# ProProject_jlc_phxc_2024-02-14.net
KiCad netlist of a schematic drawn in EasyEDA Pro
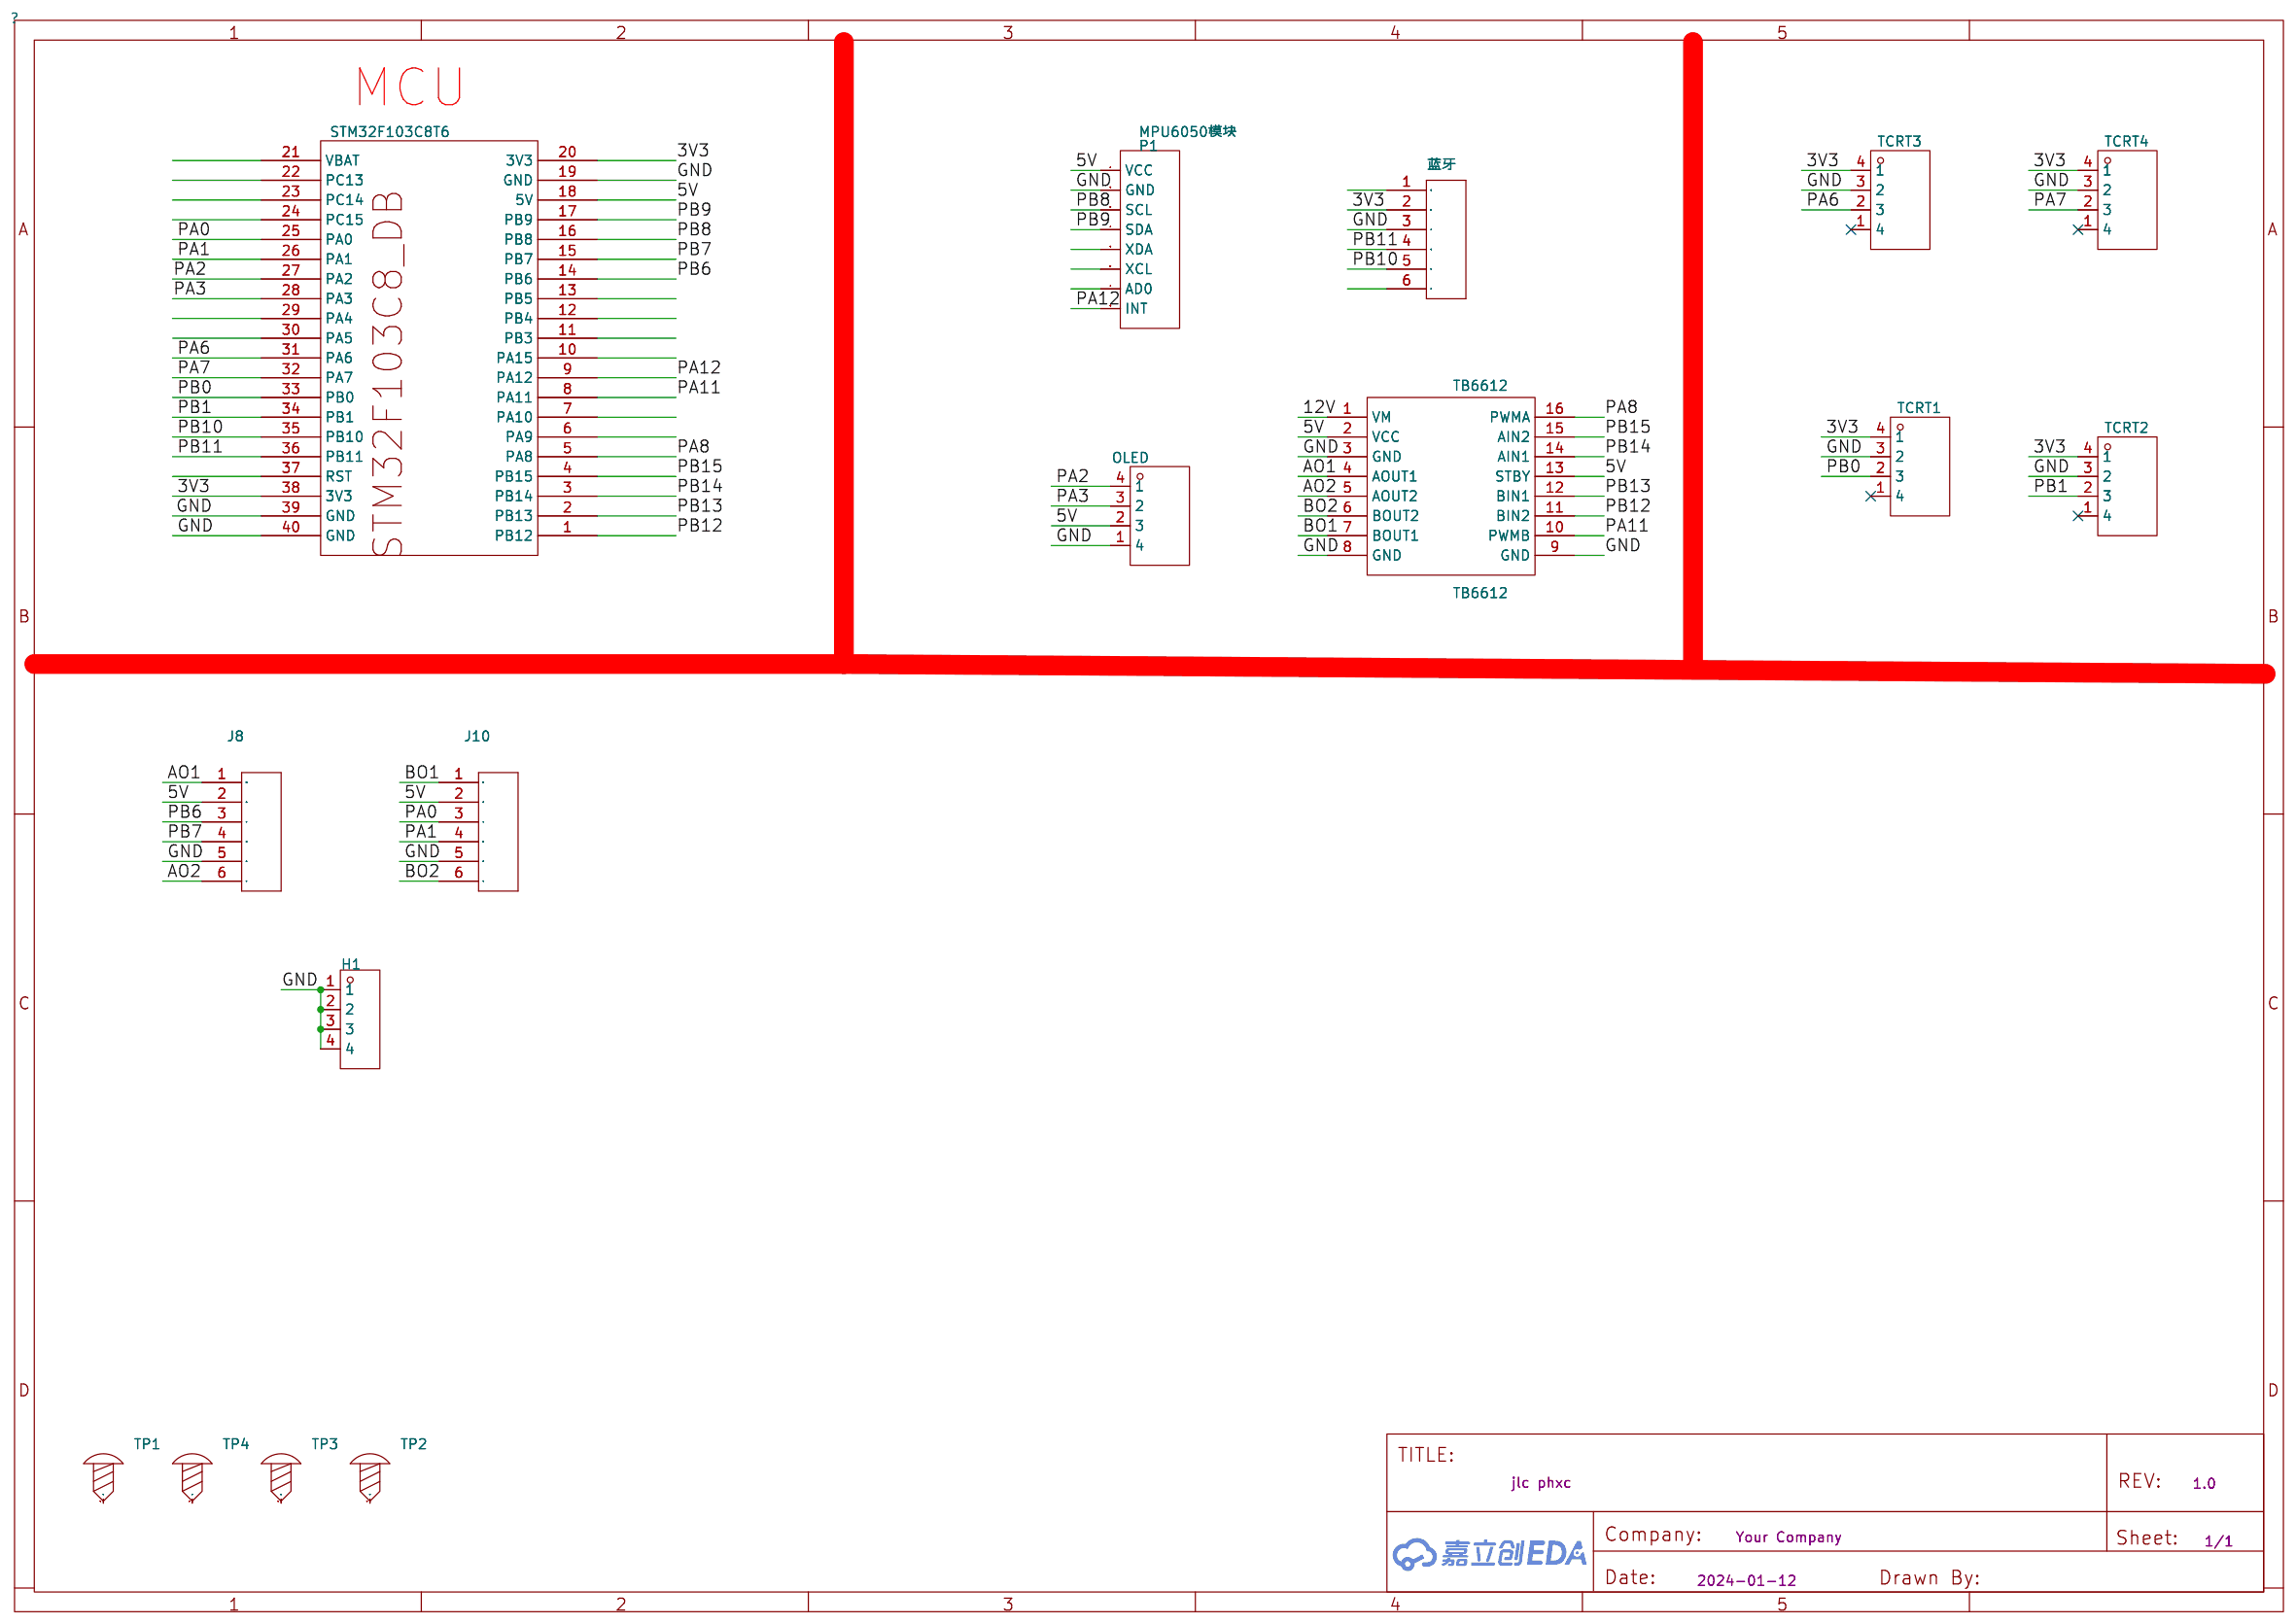
[diagram p0: schematic sheet]

(export (version "E")
  (design (tool "Eeschema 10.0.6"))
  (components
    (comp (ref "1")
      (value "TCRT1")
      (footprint "easyedapro:TCRT5000-红外循迹模块")
      (libsource (lib "easyedapro") (part "TCRT1"))
    )
    (comp (ref "2")
      (value "TCRT2")
      (footprint "easyedapro:TCRT5000-红外循迹模块")
      (libsource (lib "easyedapro") (part "TCRT2"))
    )
    (comp (ref "3")
      (value "TCRT3")
      (footprint "easyedapro:TCRT5000-红外循迹模块")
      (libsource (lib "easyedapro") (part "TCRT3"))
    )
    (comp (ref "4")
      (value "TCRT4")
      (footprint "easyedapro:TCRT5000-红外循迹模块")
      (libsource (lib "easyedapro") (part "TCRT4"))
    )
    (comp (ref "H1")
      (value "~")
      (footprint "easyedapro:HDR-TH_4P-P2.54-V-F")
      (libsource (lib "easyedapro") (part "2.54-1*4P母"))
    )
    (comp (ref "J8")
      (value "F185-1106A1BRYA1")
      (footprint "easyedapro:H6-2.54-90D-FEMALE")
      (libsource (lib "easyedapro") (part "F185-1106A1BRYA1"))
    )
    (comp (ref "J10")
      (value "F185-1106A1BRYA1")
      (footprint "easyedapro:H6-2.54-90D-FEMALE")
      (libsource (lib "easyedapro") (part "F185-1106A1BRYA1"))
    )
    (comp (ref "OLEDU1")
      (value "OLED")
      (footprint "easyedapro:0.96OLED_4P")
      (libsource (lib "easyedapro") (part "OLED"))
    )
    (comp (ref "P1")
      (value "MPU6050模块")
      (footprint "easyedapro:MPU6050模块")
      (libsource (lib "easyedapro") (part "MPU6050模块"))
    )
    (comp (ref "STMSTM32F103C8_DB")
      (value "STM32F103C8T6")
      (footprint "easyedapro:STM32F103C8T6_DB")
      (libsource (lib "easyedapro") (part "STM32F103C8_DB"))
    )
    (comp (ref "TB6612")
      (value "TB6612")
      (footprint "easyedapro:COMM-TH_TB6612")
      (libsource (lib "easyedapro") (part "TB6612"))
    )
    (comp (ref "TP1") (value "~") (footprint "easyedapro:M3螺丝") (libsource (lib "easyedapro") (part "螺丝孔")))
    (comp (ref "TP2") (value "~") (footprint "easyedapro:M3螺丝") (libsource (lib "easyedapro") (part "螺丝孔")))
    (comp (ref "TP3") (value "~") (footprint "easyedapro:M3螺丝") (libsource (lib "easyedapro") (part "螺丝孔")))
    (comp (ref "TP4") (value "~") (footprint "easyedapro:M3螺丝") (libsource (lib "easyedapro") (part "螺丝孔")))
    (comp (ref "蓝牙")
      (value "F185-1106A1BRYA1")
      (footprint "easyedapro:H6-2.54-90D-FEMALE")
      (libsource (lib "easyedapro") (part "F185-1106A1BRYA1"))
    )
  )
  (nets
    (net (code "1") (name "/3V3") (class "Default")
      (node (ref "1") (pin "4") (pinfunction "1_4") (pintype "unspecified"))
      (node (ref "2") (pin "4") (pinfunction "1_4") (pintype "unspecified"))
      (node (ref "3") (pin "4") (pinfunction "1_4") (pintype "unspecified"))
      (node (ref "4") (pin "4") (pinfunction "1_4") (pintype "unspecified"))
      (node (ref "STMSTM32F103C8_DB") (pin "20") (pinfunction "3V3_20") (pintype "unspecified"))
      (node (ref "STMSTM32F103C8_DB") (pin "38") (pinfunction "3V3_38") (pintype "unspecified"))
      (node (ref "蓝牙") (pin "2") (pinfunction "5_2") (pintype "unspecified"))
    )
    (net (code "2") (name "/5V") (class "Default")
      (node (ref "J10") (pin "2") (pinfunction "5_2") (pintype "unspecified"))
      (node (ref "J8") (pin "2") (pinfunction "5_2") (pintype "unspecified"))
      (node (ref "OLEDU1") (pin "2") (pinfunction "3_2") (pintype "unspecified"))
      (node (ref "P1") (pin "1") (pinfunction "VCC_1") (pintype "input"))
      (node (ref "STMSTM32F103C8_DB") (pin "18") (pinfunction "5V_18") (pintype "unspecified"))
      (node (ref "TB6612") (pin "13") (pinfunction "STBY_13") (pintype "unspecified"))
      (node (ref "TB6612") (pin "2") (pinfunction "VCC_2") (pintype "unspecified"))
    )
    (net (code "3") (name "/12V") (class "Default")
      (node (ref "TB6612") (pin "1") (pinfunction "VM_1") (pintype "unspecified"))
    )
    (net (code "4") (name "/AO1") (class "Default")
      (node (ref "J8") (pin "1") (pinfunction "6_1") (pintype "unspecified"))
      (node (ref "TB6612") (pin "4") (pinfunction "AOUT1_4") (pintype "unspecified"))
    )
    (net (code "5") (name "/AO2") (class "Default")
      (node (ref "J8") (pin "6") (pinfunction "1_6") (pintype "unspecified"))
      (node (ref "TB6612") (pin "5") (pinfunction "AOUT2_5") (pintype "unspecified"))
    )
    (net (code "6") (name "/BO1") (class "Default")
      (node (ref "J10") (pin "1") (pinfunction "6_1") (pintype "unspecified"))
      (node (ref "TB6612") (pin "7") (pinfunction "BOUT1_7") (pintype "unspecified"))
    )
    (net (code "7") (name "/BO2") (class "Default")
      (node (ref "J10") (pin "6") (pinfunction "1_6") (pintype "unspecified"))
      (node (ref "TB6612") (pin "6") (pinfunction "BOUT2_6") (pintype "unspecified"))
    )
    (net (code "8") (name "/GND") (class "Default")
      (node (ref "1") (pin "3") (pinfunction "2_3") (pintype "unspecified"))
      (node (ref "2") (pin "3") (pinfunction "2_3") (pintype "unspecified"))
      (node (ref "3") (pin "3") (pinfunction "2_3") (pintype "unspecified"))
      (node (ref "4") (pin "3") (pinfunction "2_3") (pintype "unspecified"))
      (node (ref "H1") (pin "1") (pinfunction "1_1") (pintype "unspecified"))
      (node (ref "H1") (pin "2") (pinfunction "2_2") (pintype "unspecified"))
      (node (ref "H1") (pin "3") (pinfunction "3_3") (pintype "unspecified"))
      (node (ref "H1") (pin "4") (pinfunction "4_4") (pintype "unspecified"))
      (node (ref "J10") (pin "5") (pinfunction "2_5") (pintype "unspecified"))
      (node (ref "J8") (pin "5") (pinfunction "2_5") (pintype "unspecified"))
      (node (ref "OLEDU1") (pin "1") (pinfunction "4_1") (pintype "unspecified"))
      (node (ref "P1") (pin "2") (pinfunction "GND_2") (pintype "input"))
      (node (ref "STMSTM32F103C8_DB") (pin "19") (pinfunction "GND_19") (pintype "unspecified"))
      (node (ref "STMSTM32F103C8_DB") (pin "39") (pinfunction "GND_39") (pintype "unspecified"))
      (node (ref "STMSTM32F103C8_DB") (pin "40") (pinfunction "GND_40") (pintype "unspecified"))
      (node (ref "TB6612") (pin "3") (pinfunction "GND_3") (pintype "unspecified"))
      (node (ref "TB6612") (pin "8") (pinfunction "GND_8") (pintype "unspecified"))
      (node (ref "TB6612") (pin "9") (pinfunction "GND_9") (pintype "unspecified"))
      (node (ref "蓝牙") (pin "3") (pinfunction "4_3") (pintype "unspecified"))
    )
    (net (code "9") (name "/PA0") (class "Default")
      (node (ref "J10") (pin "3") (pinfunction "4_3") (pintype "unspecified"))
      (node (ref "STMSTM32F103C8_DB") (pin "25") (pinfunction "PA0_25") (pintype "unspecified"))
    )
    (net (code "10") (name "/PA1") (class "Default")
      (node (ref "J10") (pin "4") (pinfunction "3_4") (pintype "unspecified"))
      (node (ref "STMSTM32F103C8_DB") (pin "26") (pinfunction "PA1_26") (pintype "unspecified"))
    )
    (net (code "11") (name "/PA2") (class "Default")
      (node (ref "OLEDU1") (pin "4") (pinfunction "1_4") (pintype "unspecified"))
      (node (ref "STMSTM32F103C8_DB") (pin "27") (pinfunction "PA2_27") (pintype "unspecified"))
    )
    (net (code "12") (name "/PA3") (class "Default")
      (node (ref "OLEDU1") (pin "3") (pinfunction "2_3") (pintype "unspecified"))
      (node (ref "STMSTM32F103C8_DB") (pin "28") (pinfunction "PA3_28") (pintype "unspecified"))
    )
    (net (code "13") (name "/PA6") (class "Default")
      (node (ref "3") (pin "2") (pinfunction "3_2") (pintype "unspecified"))
      (node (ref "STMSTM32F103C8_DB") (pin "31") (pinfunction "PA6_31") (pintype "unspecified"))
    )
    (net (code "14") (name "/PA7") (class "Default")
      (node (ref "4") (pin "2") (pinfunction "3_2") (pintype "unspecified"))
      (node (ref "STMSTM32F103C8_DB") (pin "32") (pinfunction "PA7_32") (pintype "unspecified"))
    )
    (net (code "15") (name "/PA8") (class "Default")
      (node (ref "STMSTM32F103C8_DB") (pin "5") (pinfunction "PA8_5") (pintype "unspecified"))
      (node (ref "TB6612") (pin "16") (pinfunction "PWMA_16") (pintype "unspecified"))
    )
    (net (code "16") (name "/PA11") (class "Default")
      (node (ref "STMSTM32F103C8_DB") (pin "8") (pinfunction "PA11_8") (pintype "unspecified"))
      (node (ref "TB6612") (pin "10") (pinfunction "PWMB_10") (pintype "unspecified"))
    )
    (net (code "17") (name "/PA12") (class "Default")
      (node (ref "P1") (pin "8") (pinfunction "INT_8") (pintype "input"))
      (node (ref "STMSTM32F103C8_DB") (pin "9") (pinfunction "PA12_9") (pintype "unspecified"))
    )
    (net (code "18") (name "/PB0") (class "Default")
      (node (ref "1") (pin "2") (pinfunction "3_2") (pintype "unspecified"))
      (node (ref "STMSTM32F103C8_DB") (pin "33") (pinfunction "PB0_33") (pintype "unspecified"))
    )
    (net (code "19") (name "/PB1") (class "Default")
      (node (ref "2") (pin "2") (pinfunction "3_2") (pintype "unspecified"))
      (node (ref "STMSTM32F103C8_DB") (pin "34") (pinfunction "PB1_34") (pintype "unspecified"))
    )
    (net (code "20") (name "/PB6") (class "Default")
      (node (ref "J8") (pin "3") (pinfunction "4_3") (pintype "unspecified"))
      (node (ref "STMSTM32F103C8_DB") (pin "14") (pinfunction "PB6_14") (pintype "unspecified"))
    )
    (net (code "21") (name "/PB7") (class "Default")
      (node (ref "J8") (pin "4") (pinfunction "3_4") (pintype "unspecified"))
      (node (ref "STMSTM32F103C8_DB") (pin "15") (pinfunction "PB7_15") (pintype "unspecified"))
    )
    (net (code "22") (name "/PB8") (class "Default")
      (node (ref "P1") (pin "3") (pinfunction "SCL_3") (pintype "input"))
      (node (ref "STMSTM32F103C8_DB") (pin "16") (pinfunction "PB8_16") (pintype "unspecified"))
    )
    (net (code "23") (name "/PB9") (class "Default")
      (node (ref "P1") (pin "4") (pinfunction "SDA_4") (pintype "input"))
      (node (ref "STMSTM32F103C8_DB") (pin "17") (pinfunction "PB9_17") (pintype "unspecified"))
    )
    (net (code "24") (name "/PB10") (class "Default")
      (node (ref "STMSTM32F103C8_DB") (pin "35") (pinfunction "PB10_35") (pintype "unspecified"))
      (node (ref "蓝牙") (pin "5") (pinfunction "2_5") (pintype "unspecified"))
    )
    (net (code "25") (name "/PB11") (class "Default")
      (node (ref "STMSTM32F103C8_DB") (pin "36") (pinfunction "PB11_36") (pintype "unspecified"))
      (node (ref "蓝牙") (pin "4") (pinfunction "3_4") (pintype "unspecified"))
    )
    (net (code "26") (name "/PB12") (class "Default")
      (node (ref "STMSTM32F103C8_DB") (pin "1") (pinfunction "PB12_1") (pintype "unspecified"))
      (node (ref "TB6612") (pin "11") (pinfunction "BIN2_11") (pintype "unspecified"))
    )
    (net (code "27") (name "/PB13") (class "Default")
      (node (ref "STMSTM32F103C8_DB") (pin "2") (pinfunction "PB13_2") (pintype "unspecified"))
      (node (ref "TB6612") (pin "12") (pinfunction "BIN1_12") (pintype "unspecified"))
    )
    (net (code "28") (name "/PB14") (class "Default")
      (node (ref "STMSTM32F103C8_DB") (pin "3") (pinfunction "PB14_3") (pintype "unspecified"))
      (node (ref "TB6612") (pin "14") (pinfunction "AIN1_14") (pintype "unspecified"))
    )
    (net (code "29") (name "/PB15") (class "Default")
      (node (ref "STMSTM32F103C8_DB") (pin "4") (pinfunction "PB15_4") (pintype "unspecified"))
      (node (ref "TB6612") (pin "15") (pinfunction "AIN2_15") (pintype "unspecified"))
    )
    (net (code "30") (name "unconnected-(1-4-Pad1)") (class "Default")
      (node (ref "1") (pin "1") (pinfunction "4_1") (pintype "unspecified+no_connect"))
    )
    (net (code "31") (name "unconnected-(2-4-Pad1)") (class "Default")
      (node (ref "2") (pin "1") (pinfunction "4_1") (pintype "unspecified+no_connect"))
    )
    (net (code "32") (name "unconnected-(3-4-Pad1)") (class "Default")
      (node (ref "3") (pin "1") (pinfunction "4_1") (pintype "unspecified+no_connect"))
    )
    (net (code "33") (name "unconnected-(4-4-Pad1)") (class "Default")
      (node (ref "4") (pin "1") (pinfunction "4_1") (pintype "unspecified+no_connect"))
    )
    (net (code "34") (name "unconnected-(P1-AD0-Pad7)") (class "Default")
      (node (ref "P1") (pin "7") (pinfunction "AD0_7") (pintype "input"))
    )
    (net (code "35") (name "unconnected-(P1-XCL-Pad6)") (class "Default")
      (node (ref "P1") (pin "6") (pinfunction "XCL_6") (pintype "input"))
    )
    (net (code "36") (name "unconnected-(P1-XDA-Pad5)") (class "Default")
      (node (ref "P1") (pin "5") (pinfunction "XDA_5") (pintype "input"))
    )
    (net (code "37") (name "unconnected-(STMSTM32F103C8_DB-PA4-Pad29)") (class "Default")
      (node (ref "STMSTM32F103C8_DB") (pin "29") (pinfunction "PA4_29") (pintype "unspecified"))
    )
    (net (code "38") (name "unconnected-(STMSTM32F103C8_DB-PA5-Pad30)") (class "Default")
      (node (ref "STMSTM32F103C8_DB") (pin "30") (pinfunction "PA5_30") (pintype "unspecified"))
    )
    (net (code "39") (name "unconnected-(STMSTM32F103C8_DB-PA9-Pad6)") (class "Default")
      (node (ref "STMSTM32F103C8_DB") (pin "6") (pinfunction "PA9_6") (pintype "unspecified"))
    )
    (net (code "40") (name "unconnected-(STMSTM32F103C8_DB-PA10-Pad7)") (class "Default")
      (node (ref "STMSTM32F103C8_DB") (pin "7") (pinfunction "PA10_7") (pintype "unspecified"))
    )
    (net (code "41") (name "unconnected-(STMSTM32F103C8_DB-PA15-Pad10)") (class "Default")
      (node (ref "STMSTM32F103C8_DB") (pin "10") (pinfunction "PA15_10") (pintype "unspecified"))
    )
    (net (code "42") (name "unconnected-(STMSTM32F103C8_DB-PB3-Pad11)") (class "Default")
      (node (ref "STMSTM32F103C8_DB") (pin "11") (pinfunction "PB3_11") (pintype "unspecified"))
    )
    (net (code "43") (name "unconnected-(STMSTM32F103C8_DB-PB4-Pad12)") (class "Default")
      (node (ref "STMSTM32F103C8_DB") (pin "12") (pinfunction "PB4_12") (pintype "unspecified"))
    )
    (net (code "44") (name "unconnected-(STMSTM32F103C8_DB-PB5-Pad13)") (class "Default")
      (node (ref "STMSTM32F103C8_DB") (pin "13") (pinfunction "PB5_13") (pintype "unspecified"))
    )
    (net (code "45") (name "unconnected-(STMSTM32F103C8_DB-PC13-Pad22)") (class "Default")
      (node (ref "STMSTM32F103C8_DB") (pin "22") (pinfunction "PC13_22") (pintype "unspecified"))
    )
    (net (code "46") (name "unconnected-(STMSTM32F103C8_DB-PC14-Pad23)") (class "Default")
      (node (ref "STMSTM32F103C8_DB") (pin "23") (pinfunction "PC14_23") (pintype "unspecified"))
    )
    (net (code "47") (name "unconnected-(STMSTM32F103C8_DB-PC15-Pad24)") (class "Default")
      (node (ref "STMSTM32F103C8_DB") (pin "24") (pinfunction "PC15_24") (pintype "unspecified"))
    )
    (net (code "48") (name "unconnected-(STMSTM32F103C8_DB-RST-Pad37)") (class "Default")
      (node (ref "STMSTM32F103C8_DB") (pin "37") (pinfunction "RST_37") (pintype "unspecified"))
    )
    (net (code "49") (name "unconnected-(STMSTM32F103C8_DB-VBAT-Pad21)") (class "Default")
      (node (ref "STMSTM32F103C8_DB") (pin "21") (pinfunction "VBAT_21") (pintype "unspecified"))
    )
    (net (code "50") (name "unconnected-(TP1-Pad1)") (class "Default")
      (node (ref "TP1") (pin "1") (pinfunction "1_1") (pintype "input"))
    )
    (net (code "51") (name "unconnected-(TP2-Pad1)") (class "Default")
      (node (ref "TP2") (pin "1") (pinfunction "1_1") (pintype "input"))
    )
    (net (code "52") (name "unconnected-(TP3-Pad1)") (class "Default")
      (node (ref "TP3") (pin "1") (pinfunction "1_1") (pintype "input"))
    )
    (net (code "53") (name "unconnected-(TP4-Pad1)") (class "Default")
      (node (ref "TP4") (pin "1") (pinfunction "1_1") (pintype "input"))
    )
    (net (code "54") (name "unconnected-(蓝牙-1-Pad6)") (class "Default")
      (node (ref "蓝牙") (pin "6") (pinfunction "1_6") (pintype "unspecified"))
    )
    (net (code "55") (name "unconnected-(蓝牙-6-Pad1)") (class "Default")
      (node (ref "蓝牙") (pin "1") (pinfunction "6_1") (pintype "unspecified"))
    )
  )
)
